# 5.net
KiCad netlist of a schematic drawn in Altium Designer
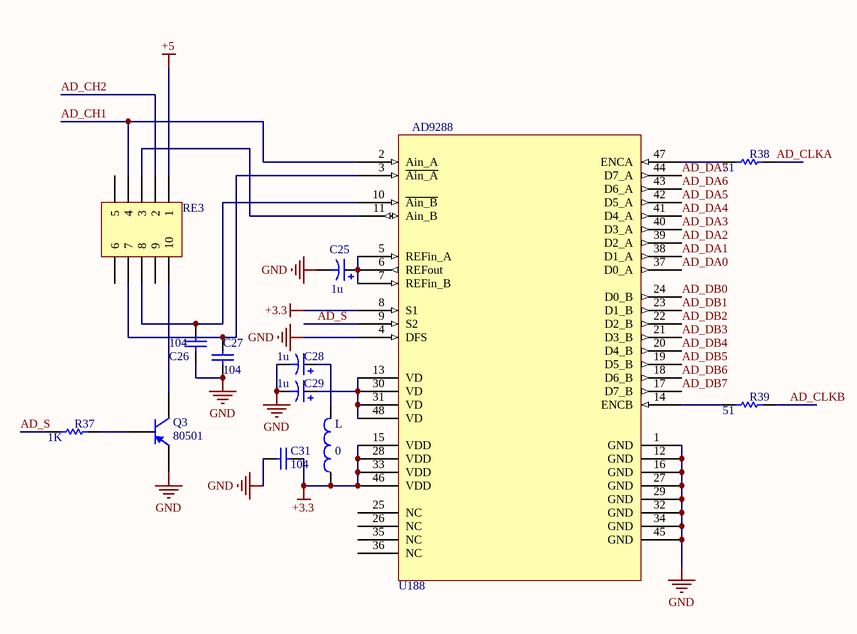
[diagram p0: 示波器原理图5.SchDoc]

(export (version "E")
  (design (tool "Eeschema 10.0.6"))
  (components
    (comp (ref "C25")
      (value "1u")
      (footprint "C0805")
      (description "Polarized Capacitor (Surface Mount)")
      (fields (field (name "PUBLISHER") "Altium Limited"))
      (libsource (lib "Miscellaneous Devices") (part "Cap Pol3"))
    )
    (comp (ref "C26")
      (value "104")
      (footprint "PCBComponent_1")
      (description "Capacitor")
      (fields (field (name "PUBLISHER") "Altium Limited"))
      (libsource (lib "Miscellaneous Devices") (part "Cap"))
    )
    (comp (ref "C27")
      (value "104")
      (footprint "PCBComponent_1")
      (description "Capacitor")
      (fields (field (name "PUBLISHER") "Altium Limited"))
      (libsource (lib "Miscellaneous Devices") (part "Cap"))
    )
    (comp (ref "C28")
      (value "1u")
      (footprint "C0805")
      (description "Polarized Capacitor (Surface Mount)")
      (fields (field (name "PUBLISHER") "Altium Limited"))
      (libsource (lib "Miscellaneous Devices") (part "Cap Pol3"))
    )
    (comp (ref "C29")
      (value "1u")
      (footprint "C0805")
      (description "Polarized Capacitor (Surface Mount)")
      (fields (field (name "PUBLISHER") "Altium Limited"))
      (libsource (lib "Miscellaneous Devices") (part "Cap Pol3"))
    )
    (comp (ref "C31")
      (value "104")
      (footprint "PCBComponent_1")
      (description "Capacitor")
      (fields (field (name "PUBLISHER") "Altium Limited"))
      (libsource (lib "Miscellaneous Devices") (part "Cap"))
    )
    (comp (ref "L")
      (value "0")
      (footprint "L0603")
      (description "Inductor")
      (fields (field (name "PUBLISHER") "Altium Limited"))
      (libsource (lib "Miscellaneous Devices") (part "Inductor"))
    )
    (comp (ref "Q3")
      (value "80501")
      (footprint "三极管贴片:PCBComponent_1")
      (description "PNP General Purpose Amplifier")
      (fields (field (name "PUBLISHER") "Altium Limited"))
      (libsource (lib "Miscellaneous Devices") (part "2N3906"))
    )
    (comp (ref "R37")
      (value "1K")
      (footprint "2012[0805]")
      (description "Semiconductor Resistor")
      (fields (field (name "PUBLISHER") "Altium Limited"))
      (libsource (lib "Miscellaneous Devices") (part "Res Semi"))
    )
    (comp (ref "R38")
      (value "51")
      (footprint "2012[0805]")
      (description "Semiconductor Resistor")
      (fields (field (name "PUBLISHER") "Altium Limited"))
      (libsource (lib "Miscellaneous Devices") (part "Res Semi"))
    )
    (comp (ref "R39")
      (value "51")
      (footprint "2012[0805]")
      (description "Semiconductor Resistor")
      (fields (field (name "PUBLISHER") "Altium Limited"))
      (libsource (lib "Miscellaneous Devices") (part "Res Semi"))
    )
    (comp (ref "RE3")
      (value "~")
      (footprint "PcbLib1:PCBComponent_1")
      (libsource (lib "TQ2-5V") (part "Component_1"))
    )
    (comp (ref "U188")
      (value "~")
      (footprint "TSQFP50P900X900X160-48N")
      (libsource (lib "AD9288") (part "Component_1"))
    )
  )
  (nets
    (net (code "1") (name "+3.3") (class "Default")
      (node (ref "C31") (pin "1") (pinfunction "1_1") (pintype "passive"))
      (node (ref "L") (pin "1") (pinfunction "1_1") (pintype "passive"))
      (node (ref "U188") (pin "15") (pinfunction "VDD_15") (pintype "passive"))
      (node (ref "U188") (pin "28") (pinfunction "VDD_28") (pintype "passive"))
      (node (ref "U188") (pin "33") (pinfunction "VDD_33") (pintype "passive"))
      (node (ref "U188") (pin "46") (pinfunction "VDD_46") (pintype "passive"))
      (node (ref "U188") (pin "8") (pinfunction "S1_8") (pintype "input"))
    )
    (net (code "2") (name "+5") (class "Default")
      (node (ref "RE3") (pin "1") (pinfunction "1_1") (pintype "passive"))
    )
    (net (code "3") (name "/AD_CH1") (class "Default")
      (node (ref "RE3") (pin "4") (pinfunction "4_4") (pintype "passive"))
      (node (ref "U188") (pin "2") (pinfunction "Ain_A_2") (pintype "input"))
    )
    (net (code "4") (name "/AD_CH2") (class "Default")
      (node (ref "RE3") (pin "2") (pinfunction "2_2") (pintype "passive"))
    )
    (net (code "5") (name "/AD_CLKA") (class "Default")
      (node (ref "R38") (pin "2") (pinfunction "2_2") (pintype "passive"))
    )
    (net (code "6") (name "/AD_CLKB") (class "Default")
      (node (ref "R39") (pin "2") (pinfunction "2_2") (pintype "passive"))
    )
    (net (code "7") (name "/AD_DA0") (class "Default")
      (node (ref "U188") (pin "37") (pinfunction "D0_A_37") (pintype "output"))
    )
    (net (code "8") (name "/AD_DA1") (class "Default")
      (node (ref "U188") (pin "38") (pinfunction "D1_A_38") (pintype "output"))
    )
    (net (code "9") (name "/AD_DA2") (class "Default")
      (node (ref "U188") (pin "39") (pinfunction "D2_A_39") (pintype "output"))
    )
    (net (code "10") (name "/AD_DA3") (class "Default")
      (node (ref "U188") (pin "40") (pinfunction "D3_A_40") (pintype "output"))
    )
    (net (code "11") (name "/AD_DA4") (class "Default")
      (node (ref "U188") (pin "41") (pinfunction "D4_A_41") (pintype "output"))
    )
    (net (code "12") (name "/AD_DA5") (class "Default")
      (node (ref "U188") (pin "42") (pinfunction "D5_A_42") (pintype "output"))
    )
    (net (code "13") (name "/AD_DA6") (class "Default")
      (node (ref "U188") (pin "43") (pinfunction "D6_A_43") (pintype "output"))
    )
    (net (code "14") (name "/AD_DA7") (class "Default")
      (node (ref "U188") (pin "44") (pinfunction "D7_A_44") (pintype "output"))
    )
    (net (code "15") (name "/AD_DB0") (class "Default")
      (node (ref "U188") (pin "24") (pinfunction "D0_B_24") (pintype "output"))
    )
    (net (code "16") (name "/AD_DB1") (class "Default")
      (node (ref "U188") (pin "23") (pinfunction "D1_B_23") (pintype "output"))
    )
    (net (code "17") (name "/AD_DB2") (class "Default")
      (node (ref "U188") (pin "22") (pinfunction "D2_B_22") (pintype "output"))
    )
    (net (code "18") (name "/AD_DB3") (class "Default")
      (node (ref "U188") (pin "21") (pinfunction "D3_B_21") (pintype "output"))
    )
    (net (code "19") (name "/AD_DB4") (class "Default")
      (node (ref "U188") (pin "20") (pinfunction "D4_B_20") (pintype "output"))
    )
    (net (code "20") (name "/AD_DB5") (class "Default")
      (node (ref "U188") (pin "19") (pinfunction "D5_B_19") (pintype "output"))
    )
    (net (code "21") (name "/AD_DB6") (class "Default")
      (node (ref "U188") (pin "18") (pinfunction "D6_B_18") (pintype "output"))
    )
    (net (code "22") (name "/AD_DB7") (class "Default")
      (node (ref "U188") (pin "17") (pinfunction "D7_B_17") (pintype "output"))
    )
    (net (code "23") (name "/AD_S") (class "Default")
      (node (ref "R37") (pin "1") (pinfunction "1_1") (pintype "passive"))
      (node (ref "U188") (pin "9") (pinfunction "S2_9") (pintype "input"))
    )
    (net (code "24") (name "GND") (class "Default")
      (node (ref "C25") (pin "2") (pinfunction "2_2") (pintype "passive"))
      (node (ref "C26") (pin "2") (pinfunction "2_2") (pintype "passive"))
      (node (ref "C27") (pin "2") (pinfunction "2_2") (pintype "passive"))
      (node (ref "C28") (pin "2") (pinfunction "2_2") (pintype "passive"))
      (node (ref "C29") (pin "2") (pinfunction "2_2") (pintype "passive"))
      (node (ref "C31") (pin "2") (pinfunction "2_2") (pintype "passive"))
      (node (ref "Q3") (pin "1") (pinfunction "E_1") (pintype "passive"))
      (node (ref "U188") (pin "1") (pinfunction "GND_1") (pintype "passive"))
      (node (ref "U188") (pin "12") (pinfunction "GND_12") (pintype "passive"))
      (node (ref "U188") (pin "16") (pinfunction "GND_16") (pintype "passive"))
      (node (ref "U188") (pin "27") (pinfunction "GND_27") (pintype "passive"))
      (node (ref "U188") (pin "29") (pinfunction "GND_29") (pintype "passive"))
      (node (ref "U188") (pin "32") (pinfunction "GND_32") (pintype "passive"))
      (node (ref "U188") (pin "34") (pinfunction "GND_34") (pintype "passive"))
      (node (ref "U188") (pin "4") (pinfunction "DFS_4") (pintype "input"))
      (node (ref "U188") (pin "45") (pinfunction "GND_45") (pintype "passive"))
    )
    (net (code "25") (name "Net-(C28-Pad1)") (class "Default")
      (node (ref "C28") (pin "1") (pinfunction "1_1") (pintype "passive"))
      (node (ref "L") (pin "2") (pinfunction "2_2") (pintype "passive"))
    )
    (net (code "26") (name "Net-(C29-Pad1)") (class "Default")
      (node (ref "C29") (pin "1") (pinfunction "1_1") (pintype "passive"))
      (node (ref "U188") (pin "13") (pinfunction "VD_13") (pintype "passive"))
      (node (ref "U188") (pin "30") (pinfunction "VD_30") (pintype "passive"))
      (node (ref "U188") (pin "31") (pinfunction "VD_31") (pintype "passive"))
      (node (ref "U188") (pin "48") (pinfunction "VD_48") (pintype "passive"))
    )
    (net (code "27") (name "Net-(Q3-B)") (class "Default")
      (node (ref "Q3") (pin "2") (pinfunction "B_2") (pintype "passive"))
      (node (ref "R37") (pin "2") (pinfunction "2_2") (pintype "passive"))
    )
    (net (code "28") (name "Net-(Q3-C)") (class "Default")
      (node (ref "Q3") (pin "3") (pinfunction "C_3") (pintype "passive"))
      (node (ref "RE3") (pin "10") (pinfunction "10_10") (pintype "passive"))
    )
    (net (code "29") (name "Net-(U188-Ain_B)") (class "Default")
      (node (ref "RE3") (pin "3") (pinfunction "3_3") (pintype "passive"))
      (node (ref "U188") (pin "11") (pinfunction "Ain_B_11") (pintype "bidirectional"))
    )
    (net (code "30") (name "Net-(U188-ENCA)") (class "Default")
      (node (ref "R38") (pin "1") (pinfunction "1_1") (pintype "passive"))
      (node (ref "U188") (pin "47") (pinfunction "ENCA_47") (pintype "input"))
    )
    (net (code "31") (name "Net-(U188-ENCB)") (class "Default")
      (node (ref "R39") (pin "1") (pinfunction "1_1") (pintype "passive"))
      (node (ref "U188") (pin "14") (pinfunction "ENCB_14") (pintype "input"))
    )
    (net (code "32") (name "Net-(U188-REFin_A)") (class "Default")
      (node (ref "C25") (pin "1") (pinfunction "1_1") (pintype "passive"))
      (node (ref "U188") (pin "5") (pinfunction "REFin_A_5") (pintype "input"))
      (node (ref "U188") (pin "6") (pinfunction "REFout_6") (pintype "output"))
      (node (ref "U188") (pin "7") (pinfunction "REFin_B_7") (pintype "input"))
    )
    (net (code "33") (name "Net-(U188-~{Ain_A})") (class "Default")
      (node (ref "C27") (pin "1") (pinfunction "1_1") (pintype "passive"))
      (node (ref "RE3") (pin "7") (pinfunction "7_7") (pintype "passive"))
      (node (ref "U188") (pin "3") (pinfunction "~{Ain_A}_3") (pintype "input"))
    )
    (net (code "34") (name "Net-(U188-~{Ain_B})") (class "Default")
      (node (ref "C26") (pin "1") (pinfunction "1_1") (pintype "passive"))
      (node (ref "RE3") (pin "8") (pinfunction "8_8") (pintype "passive"))
      (node (ref "U188") (pin "10") (pinfunction "~{Ain_B}_10") (pintype "input"))
    )
    (net (code "35") (name "unconnected-(RE3-Pad5)") (class "Default")
      (node (ref "RE3") (pin "5") (pinfunction "5_5") (pintype "passive"))
    )
    (net (code "36") (name "unconnected-(RE3-Pad6)") (class "Default")
      (node (ref "RE3") (pin "6") (pinfunction "6_6") (pintype "passive"))
    )
    (net (code "37") (name "unconnected-(RE3-Pad9)") (class "Default")
      (node (ref "RE3") (pin "9") (pinfunction "9_9") (pintype "passive"))
    )
    (net (code "38") (name "unconnected-(U188-NC-Pad25)") (class "Default")
      (node (ref "U188") (pin "25") (pinfunction "NC_25") (pintype "passive"))
    )
    (net (code "39") (name "unconnected-(U188-NC-Pad26)") (class "Default")
      (node (ref "U188") (pin "26") (pinfunction "NC_26") (pintype "passive"))
    )
    (net (code "40") (name "unconnected-(U188-NC-Pad35)") (class "Default")
      (node (ref "U188") (pin "35") (pinfunction "NC_35") (pintype "passive"))
    )
    (net (code "41") (name "unconnected-(U188-NC-Pad36)") (class "Default")
      (node (ref "U188") (pin "36") (pinfunction "NC_36") (pintype "passive"))
    )
  )
)
